# MatrixDriver.net
KiCad netlist of a schematic drawn in Altium Designer
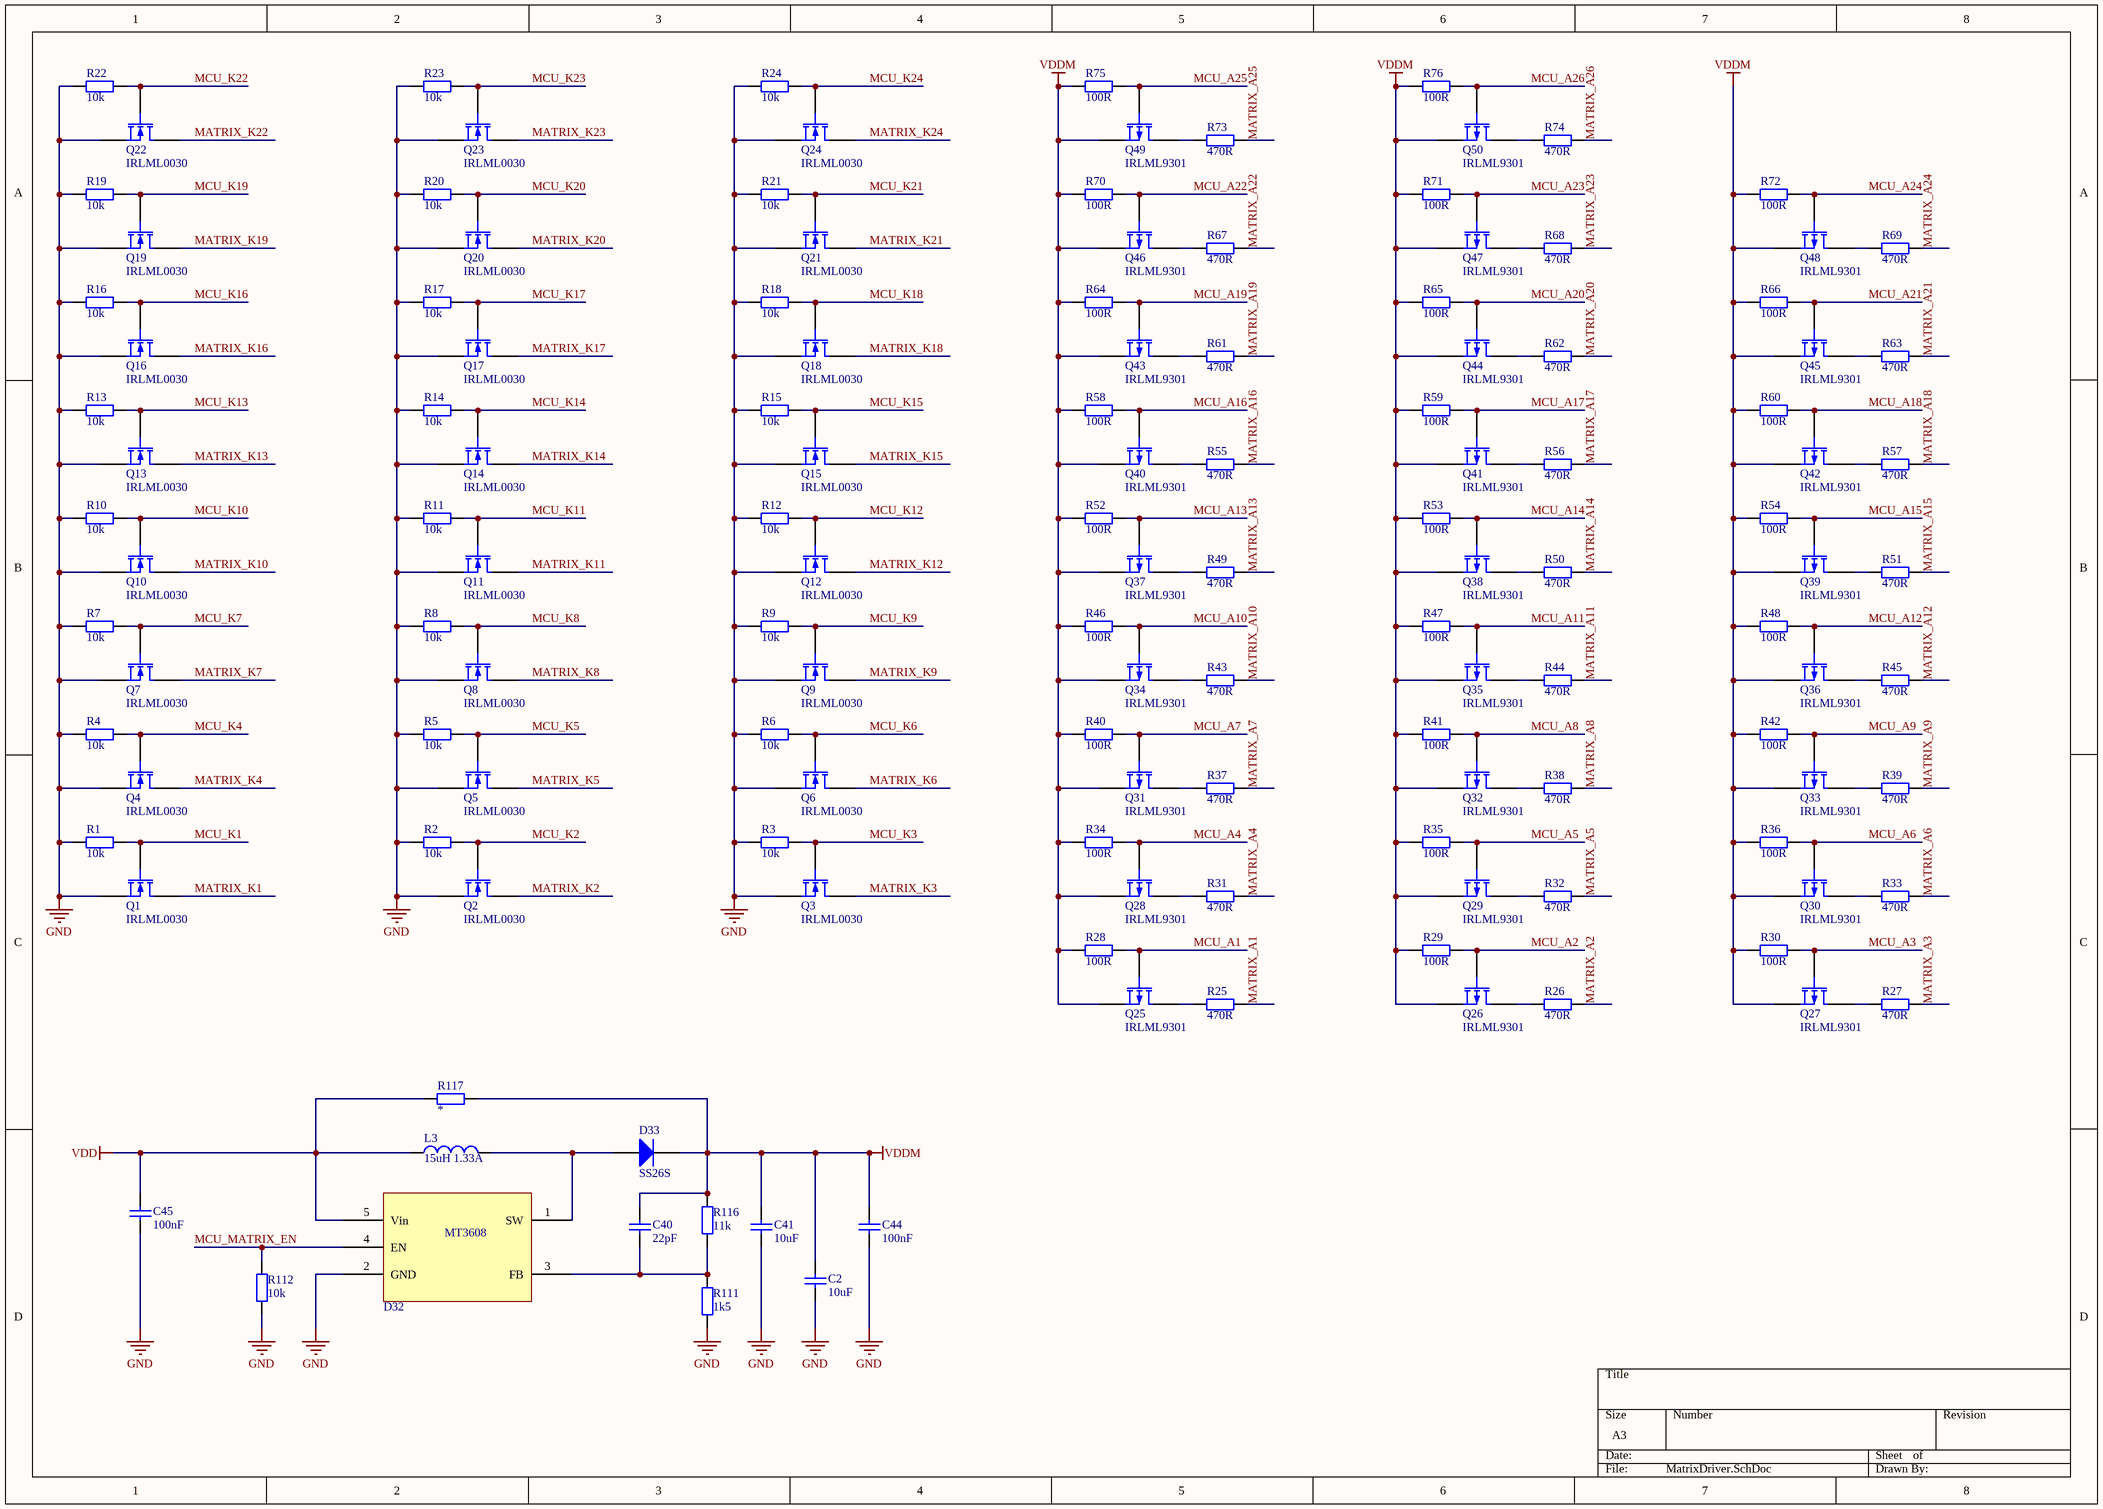
[diagram p0: MatrixDriver.SchDoc]

(export (version "E")
  (design (tool "Eeschema 10.0.6"))
  (components
    (comp (ref "C2")
      (value "10uF")
      (footprint "c1206")
      (description "Capacitor")
      (fields (field (name "Comment") "Cap"))
      (libsource (lib "Lib_Sch") (part "Cap"))
    )
    (comp (ref "C40")
      (value "22pF")
      (footprint "C0603")
      (description "Capacitor")
      (fields (field (name "Comment") "Cap"))
      (libsource (lib "Lib_Sch") (part "Cap"))
    )
    (comp (ref "C41")
      (value "10uF")
      (footprint "c1206")
      (description "Capacitor")
      (fields (field (name "Comment") "Cap"))
      (libsource (lib "Lib_Sch") (part "Cap"))
    )
    (comp (ref "C44")
      (value "100nF")
      (footprint "C0603")
      (description "Capacitor")
      (fields (field (name "Comment") "Cap"))
      (libsource (lib "Lib_Sch") (part "Cap"))
    )
    (comp (ref "C45")
      (value "100nF")
      (footprint "C0603")
      (description "Capacitor")
      (fields (field (name "Comment") "Cap"))
      (libsource (lib "Lib_Sch") (part "Cap"))
    )
    (comp (ref "D32") (value "MT3608") (footprint "SOT23-6_L") (libsource (lib "Lib_Sch") (part "MT3608")))
    (comp (ref "D33")
      (value "SS26S")
      (footprint "DO-214AB")
      (description "Default Diode")
      (libsource (lib "Lib_Sch") (part "Diode"))
    )
    (comp (ref "L3")
      (value "15uH 1.33A")
      (footprint "DE0703")
      (description "DE0703-15")
      (libsource (lib "Lib_Sch") (part "Inductor"))
    )
    (comp (ref "Q1")
      (value "IRLML0030")
      (footprint "sot23")
      (description "N-Channel MOSFET")
      (libsource (lib "Lib_Sch") (part "MOSFET-N"))
    )
    (comp (ref "Q2")
      (value "IRLML0030")
      (footprint "sot23")
      (description "N-Channel MOSFET")
      (libsource (lib "Lib_Sch") (part "MOSFET-N"))
    )
    (comp (ref "Q3")
      (value "IRLML0030")
      (footprint "sot23")
      (description "N-Channel MOSFET")
      (libsource (lib "Lib_Sch") (part "MOSFET-N"))
    )
    (comp (ref "Q4")
      (value "IRLML0030")
      (footprint "sot23")
      (description "N-Channel MOSFET")
      (libsource (lib "Lib_Sch") (part "MOSFET-N"))
    )
    (comp (ref "Q5")
      (value "IRLML0030")
      (footprint "sot23")
      (description "N-Channel MOSFET")
      (libsource (lib "Lib_Sch") (part "MOSFET-N"))
    )
    (comp (ref "Q6")
      (value "IRLML0030")
      (footprint "sot23")
      (description "N-Channel MOSFET")
      (libsource (lib "Lib_Sch") (part "MOSFET-N"))
    )
    (comp (ref "Q7")
      (value "IRLML0030")
      (footprint "sot23")
      (description "N-Channel MOSFET")
      (libsource (lib "Lib_Sch") (part "MOSFET-N"))
    )
    (comp (ref "Q8")
      (value "IRLML0030")
      (footprint "sot23")
      (description "N-Channel MOSFET")
      (libsource (lib "Lib_Sch") (part "MOSFET-N"))
    )
    (comp (ref "Q9")
      (value "IRLML0030")
      (footprint "sot23")
      (description "N-Channel MOSFET")
      (libsource (lib "Lib_Sch") (part "MOSFET-N"))
    )
    (comp (ref "Q10")
      (value "IRLML0030")
      (footprint "sot23")
      (description "N-Channel MOSFET")
      (libsource (lib "Lib_Sch") (part "MOSFET-N"))
    )
    (comp (ref "Q11")
      (value "IRLML0030")
      (footprint "sot23")
      (description "N-Channel MOSFET")
      (libsource (lib "Lib_Sch") (part "MOSFET-N"))
    )
    (comp (ref "Q12")
      (value "IRLML0030")
      (footprint "sot23")
      (description "N-Channel MOSFET")
      (libsource (lib "Lib_Sch") (part "MOSFET-N"))
    )
    (comp (ref "Q13")
      (value "IRLML0030")
      (footprint "sot23")
      (description "N-Channel MOSFET")
      (libsource (lib "Lib_Sch") (part "MOSFET-N"))
    )
    (comp (ref "Q14")
      (value "IRLML0030")
      (footprint "sot23")
      (description "N-Channel MOSFET")
      (libsource (lib "Lib_Sch") (part "MOSFET-N"))
    )
    (comp (ref "Q15")
      (value "IRLML0030")
      (footprint "sot23")
      (description "N-Channel MOSFET")
      (libsource (lib "Lib_Sch") (part "MOSFET-N"))
    )
    (comp (ref "Q16")
      (value "IRLML0030")
      (footprint "sot23")
      (description "N-Channel MOSFET")
      (libsource (lib "Lib_Sch") (part "MOSFET-N"))
    )
    (comp (ref "Q17")
      (value "IRLML0030")
      (footprint "sot23")
      (description "N-Channel MOSFET")
      (libsource (lib "Lib_Sch") (part "MOSFET-N"))
    )
    (comp (ref "Q18")
      (value "IRLML0030")
      (footprint "sot23")
      (description "N-Channel MOSFET")
      (libsource (lib "Lib_Sch") (part "MOSFET-N"))
    )
    (comp (ref "Q19")
      (value "IRLML0030")
      (footprint "sot23")
      (description "N-Channel MOSFET")
      (libsource (lib "Lib_Sch") (part "MOSFET-N"))
    )
    (comp (ref "Q20")
      (value "IRLML0030")
      (footprint "sot23")
      (description "N-Channel MOSFET")
      (libsource (lib "Lib_Sch") (part "MOSFET-N"))
    )
    (comp (ref "Q21")
      (value "IRLML0030")
      (footprint "sot23")
      (description "N-Channel MOSFET")
      (libsource (lib "Lib_Sch") (part "MOSFET-N"))
    )
    (comp (ref "Q22")
      (value "IRLML0030")
      (footprint "sot23")
      (description "N-Channel MOSFET")
      (libsource (lib "Lib_Sch") (part "MOSFET-N"))
    )
    (comp (ref "Q23")
      (value "IRLML0030")
      (footprint "sot23")
      (description "N-Channel MOSFET")
      (libsource (lib "Lib_Sch") (part "MOSFET-N"))
    )
    (comp (ref "Q24")
      (value "IRLML0030")
      (footprint "sot23")
      (description "N-Channel MOSFET")
      (libsource (lib "Lib_Sch") (part "MOSFET-N"))
    )
    (comp (ref "Q25")
      (value "IRLML9301")
      (footprint "sot23")
      (description "P-Channel MOSFET")
      (libsource (lib "Lib_Sch") (part "MOSFET-P"))
    )
    (comp (ref "Q26")
      (value "IRLML9301")
      (footprint "sot23")
      (description "P-Channel MOSFET")
      (libsource (lib "Lib_Sch") (part "MOSFET-P"))
    )
    (comp (ref "Q27")
      (value "IRLML9301")
      (footprint "sot23")
      (description "P-Channel MOSFET")
      (libsource (lib "Lib_Sch") (part "MOSFET-P"))
    )
    (comp (ref "Q28")
      (value "IRLML9301")
      (footprint "sot23")
      (description "P-Channel MOSFET")
      (libsource (lib "Lib_Sch") (part "MOSFET-P"))
    )
    (comp (ref "Q29")
      (value "IRLML9301")
      (footprint "sot23")
      (description "P-Channel MOSFET")
      (libsource (lib "Lib_Sch") (part "MOSFET-P"))
    )
    (comp (ref "Q30")
      (value "IRLML9301")
      (footprint "sot23")
      (description "P-Channel MOSFET")
      (libsource (lib "Lib_Sch") (part "MOSFET-P"))
    )
    (comp (ref "Q31")
      (value "IRLML9301")
      (footprint "sot23")
      (description "P-Channel MOSFET")
      (libsource (lib "Lib_Sch") (part "MOSFET-P"))
    )
    (comp (ref "Q32")
      (value "IRLML9301")
      (footprint "sot23")
      (description "P-Channel MOSFET")
      (libsource (lib "Lib_Sch") (part "MOSFET-P"))
    )
    (comp (ref "Q33")
      (value "IRLML9301")
      (footprint "sot23")
      (description "P-Channel MOSFET")
      (libsource (lib "Lib_Sch") (part "MOSFET-P"))
    )
    (comp (ref "Q34")
      (value "IRLML9301")
      (footprint "sot23")
      (description "P-Channel MOSFET")
      (libsource (lib "Lib_Sch") (part "MOSFET-P"))
    )
    (comp (ref "Q35")
      (value "IRLML9301")
      (footprint "sot23")
      (description "P-Channel MOSFET")
      (libsource (lib "Lib_Sch") (part "MOSFET-P"))
    )
    (comp (ref "Q36")
      (value "IRLML9301")
      (footprint "sot23")
      (description "P-Channel MOSFET")
      (libsource (lib "Lib_Sch") (part "MOSFET-P"))
    )
    (comp (ref "Q37")
      (value "IRLML9301")
      (footprint "sot23")
      (description "P-Channel MOSFET")
      (libsource (lib "Lib_Sch") (part "MOSFET-P"))
    )
    (comp (ref "Q38")
      (value "IRLML9301")
      (footprint "sot23")
      (description "P-Channel MOSFET")
      (libsource (lib "Lib_Sch") (part "MOSFET-P"))
    )
    (comp (ref "Q39")
      (value "IRLML9301")
      (footprint "sot23")
      (description "P-Channel MOSFET")
      (libsource (lib "Lib_Sch") (part "MOSFET-P"))
    )
    (comp (ref "Q40")
      (value "IRLML9301")
      (footprint "sot23")
      (description "P-Channel MOSFET")
      (libsource (lib "Lib_Sch") (part "MOSFET-P"))
    )
    (comp (ref "Q41")
      (value "IRLML9301")
      (footprint "sot23")
      (description "P-Channel MOSFET")
      (libsource (lib "Lib_Sch") (part "MOSFET-P"))
    )
    (comp (ref "Q42")
      (value "IRLML9301")
      (footprint "sot23")
      (description "P-Channel MOSFET")
      (libsource (lib "Lib_Sch") (part "MOSFET-P"))
    )
    (comp (ref "Q43")
      (value "IRLML9301")
      (footprint "sot23")
      (description "P-Channel MOSFET")
      (libsource (lib "Lib_Sch") (part "MOSFET-P"))
    )
    (comp (ref "Q44")
      (value "IRLML9301")
      (footprint "sot23")
      (description "P-Channel MOSFET")
      (libsource (lib "Lib_Sch") (part "MOSFET-P"))
    )
    (comp (ref "Q45")
      (value "IRLML9301")
      (footprint "sot23")
      (description "P-Channel MOSFET")
      (libsource (lib "Lib_Sch") (part "MOSFET-P"))
    )
    (comp (ref "Q46")
      (value "IRLML9301")
      (footprint "sot23")
      (description "P-Channel MOSFET")
      (libsource (lib "Lib_Sch") (part "MOSFET-P"))
    )
    (comp (ref "Q47")
      (value "IRLML9301")
      (footprint "sot23")
      (description "P-Channel MOSFET")
      (libsource (lib "Lib_Sch") (part "MOSFET-P"))
    )
    (comp (ref "Q48")
      (value "IRLML9301")
      (footprint "sot23")
      (description "P-Channel MOSFET")
      (libsource (lib "Lib_Sch") (part "MOSFET-P"))
    )
    (comp (ref "Q49")
      (value "IRLML9301")
      (footprint "sot23")
      (description "P-Channel MOSFET")
      (libsource (lib "Lib_Sch") (part "MOSFET-P"))
    )
    (comp (ref "Q50")
      (value "IRLML9301")
      (footprint "sot23")
      (description "P-Channel MOSFET")
      (libsource (lib "Lib_Sch") (part "MOSFET-P"))
    )
    (comp (ref "R1")
      (value "10k")
      (footprint "r0603")
      (description "Resistor")
      (libsource (lib "Lib_Sch") (part "Resistor"))
    )
    (comp (ref "R2")
      (value "10k")
      (footprint "r0603")
      (description "Resistor")
      (libsource (lib "Lib_Sch") (part "Resistor"))
    )
    (comp (ref "R3")
      (value "10k")
      (footprint "r0603")
      (description "Resistor")
      (libsource (lib "Lib_Sch") (part "Resistor"))
    )
    (comp (ref "R4")
      (value "10k")
      (footprint "r0603")
      (description "Resistor")
      (libsource (lib "Lib_Sch") (part "Resistor"))
    )
    (comp (ref "R5")
      (value "10k")
      (footprint "r0603")
      (description "Resistor")
      (libsource (lib "Lib_Sch") (part "Resistor"))
    )
    (comp (ref "R6")
      (value "10k")
      (footprint "r0603")
      (description "Resistor")
      (libsource (lib "Lib_Sch") (part "Resistor"))
    )
    (comp (ref "R7")
      (value "10k")
      (footprint "r0603")
      (description "Resistor")
      (libsource (lib "Lib_Sch") (part "Resistor"))
    )
    (comp (ref "R8")
      (value "10k")
      (footprint "r0603")
      (description "Resistor")
      (libsource (lib "Lib_Sch") (part "Resistor"))
    )
    (comp (ref "R9")
      (value "10k")
      (footprint "r0603")
      (description "Resistor")
      (libsource (lib "Lib_Sch") (part "Resistor"))
    )
    (comp (ref "R10")
      (value "10k")
      (footprint "r0603")
      (description "Resistor")
      (libsource (lib "Lib_Sch") (part "Resistor"))
    )
    (comp (ref "R11")
      (value "10k")
      (footprint "r0603")
      (description "Resistor")
      (libsource (lib "Lib_Sch") (part "Resistor"))
    )
    (comp (ref "R12")
      (value "10k")
      (footprint "r0603")
      (description "Resistor")
      (libsource (lib "Lib_Sch") (part "Resistor"))
    )
    (comp (ref "R13")
      (value "10k")
      (footprint "r0603")
      (description "Resistor")
      (libsource (lib "Lib_Sch") (part "Resistor"))
    )
    (comp (ref "R14")
      (value "10k")
      (footprint "r0603")
      (description "Resistor")
      (libsource (lib "Lib_Sch") (part "Resistor"))
    )
    (comp (ref "R15")
      (value "10k")
      (footprint "r0603")
      (description "Resistor")
      (libsource (lib "Lib_Sch") (part "Resistor"))
    )
    (comp (ref "R16")
      (value "10k")
      (footprint "r0603")
      (description "Resistor")
      (libsource (lib "Lib_Sch") (part "Resistor"))
    )
    (comp (ref "R17")
      (value "10k")
      (footprint "r0603")
      (description "Resistor")
      (libsource (lib "Lib_Sch") (part "Resistor"))
    )
    (comp (ref "R18")
      (value "10k")
      (footprint "r0603")
      (description "Resistor")
      (libsource (lib "Lib_Sch") (part "Resistor"))
    )
    (comp (ref "R19")
      (value "10k")
      (footprint "r0603")
      (description "Resistor")
      (libsource (lib "Lib_Sch") (part "Resistor"))
    )
    (comp (ref "R20")
      (value "10k")
      (footprint "r0603")
      (description "Resistor")
      (libsource (lib "Lib_Sch") (part "Resistor"))
    )
    (comp (ref "R21")
      (value "10k")
      (footprint "r0603")
      (description "Resistor")
      (libsource (lib "Lib_Sch") (part "Resistor"))
    )
    (comp (ref "R22")
      (value "10k")
      (footprint "r0603")
      (description "Resistor")
      (libsource (lib "Lib_Sch") (part "Resistor"))
    )
    (comp (ref "R23")
      (value "10k")
      (footprint "r0603")
      (description "Resistor")
      (libsource (lib "Lib_Sch") (part "Resistor"))
    )
    (comp (ref "R24")
      (value "10k")
      (footprint "r0603")
      (description "Resistor")
      (libsource (lib "Lib_Sch") (part "Resistor"))
    )
    (comp (ref "R25")
      (value "470R")
      (footprint "r0603")
      (description "Resistor")
      (libsource (lib "Lib_Sch") (part "Resistor"))
    )
    (comp (ref "R26")
      (value "470R")
      (footprint "r0603")
      (description "Resistor")
      (libsource (lib "Lib_Sch") (part "Resistor"))
    )
    (comp (ref "R27")
      (value "470R")
      (footprint "r0603")
      (description "Resistor")
      (libsource (lib "Lib_Sch") (part "Resistor"))
    )
    (comp (ref "R28")
      (value "100R")
      (footprint "r0603")
      (description "Resistor")
      (libsource (lib "Lib_Sch") (part "Resistor"))
    )
    (comp (ref "R29")
      (value "100R")
      (footprint "r0603")
      (description "Resistor")
      (libsource (lib "Lib_Sch") (part "Resistor"))
    )
    (comp (ref "R30")
      (value "100R")
      (footprint "r0603")
      (description "Resistor")
      (libsource (lib "Lib_Sch") (part "Resistor"))
    )
    (comp (ref "R31")
      (value "470R")
      (footprint "r0603")
      (description "Resistor")
      (libsource (lib "Lib_Sch") (part "Resistor"))
    )
    (comp (ref "R32")
      (value "470R")
      (footprint "r0603")
      (description "Resistor")
      (libsource (lib "Lib_Sch") (part "Resistor"))
    )
    (comp (ref "R33")
      (value "470R")
      (footprint "r0603")
      (description "Resistor")
      (libsource (lib "Lib_Sch") (part "Resistor"))
    )
    (comp (ref "R34")
      (value "100R")
      (footprint "r0603")
      (description "Resistor")
      (libsource (lib "Lib_Sch") (part "Resistor"))
    )
    (comp (ref "R35")
      (value "100R")
      (footprint "r0603")
      (description "Resistor")
      (libsource (lib "Lib_Sch") (part "Resistor"))
    )
    (comp (ref "R36")
      (value "100R")
      (footprint "r0603")
      (description "Resistor")
      (libsource (lib "Lib_Sch") (part "Resistor"))
    )
    (comp (ref "R37")
      (value "470R")
      (footprint "r0603")
      (description "Resistor")
      (libsource (lib "Lib_Sch") (part "Resistor"))
    )
    (comp (ref "R38")
      (value "470R")
      (footprint "r0603")
      (description "Resistor")
      (libsource (lib "Lib_Sch") (part "Resistor"))
    )
    (comp (ref "R39")
      (value "470R")
      (footprint "r0603")
      (description "Resistor")
      (libsource (lib "Lib_Sch") (part "Resistor"))
    )
    (comp (ref "R40")
      (value "100R")
      (footprint "r0603")
      (description "Resistor")
      (libsource (lib "Lib_Sch") (part "Resistor"))
    )
    (comp (ref "R41")
      (value "100R")
      (footprint "r0603")
      (description "Resistor")
      (libsource (lib "Lib_Sch") (part "Resistor"))
    )
    (comp (ref "R42")
      (value "100R")
      (footprint "r0603")
      (description "Resistor")
      (libsource (lib "Lib_Sch") (part "Resistor"))
    )
    (comp (ref "R43")
      (value "470R")
      (footprint "r0603")
      (description "Resistor")
      (libsource (lib "Lib_Sch") (part "Resistor"))
    )
    (comp (ref "R44")
      (value "470R")
      (footprint "r0603")
      (description "Resistor")
      (libsource (lib "Lib_Sch") (part "Resistor"))
    )
    (comp (ref "R45")
      (value "470R")
      (footprint "r0603")
      (description "Resistor")
      (libsource (lib "Lib_Sch") (part "Resistor"))
    )
    (comp (ref "R46")
      (value "100R")
      (footprint "r0603")
      (description "Resistor")
      (libsource (lib "Lib_Sch") (part "Resistor"))
    )
    (comp (ref "R47")
      (value "100R")
      (footprint "r0603")
      (description "Resistor")
      (libsource (lib "Lib_Sch") (part "Resistor"))
    )
    (comp (ref "R48")
      (value "100R")
      (footprint "r0603")
      (description "Resistor")
      (libsource (lib "Lib_Sch") (part "Resistor"))
    )
    (comp (ref "R49")
      (value "470R")
      (footprint "r0603")
      (description "Resistor")
      (libsource (lib "Lib_Sch") (part "Resistor"))
    )
    (comp (ref "R50")
      (value "470R")
      (footprint "r0603")
      (description "Resistor")
      (libsource (lib "Lib_Sch") (part "Resistor"))
    )
    (comp (ref "R51")
      (value "470R")
      (footprint "r0603")
      (description "Resistor")
      (libsource (lib "Lib_Sch") (part "Resistor"))
    )
    (comp (ref "R52")
      (value "100R")
      (footprint "r0603")
      (description "Resistor")
      (libsource (lib "Lib_Sch") (part "Resistor"))
    )
    (comp (ref "R53")
      (value "100R")
      (footprint "r0603")
      (description "Resistor")
      (libsource (lib "Lib_Sch") (part "Resistor"))
    )
    (comp (ref "R54")
      (value "100R")
      (footprint "r0603")
      (description "Resistor")
      (libsource (lib "Lib_Sch") (part "Resistor"))
    )
    (comp (ref "R55")
      (value "470R")
      (footprint "r0603")
      (description "Resistor")
      (libsource (lib "Lib_Sch") (part "Resistor"))
    )
    (comp (ref "R56")
      (value "470R")
      (footprint "r0603")
      (description "Resistor")
      (libsource (lib "Lib_Sch") (part "Resistor"))
    )
    (comp (ref "R57")
      (value "470R")
      (footprint "r0603")
      (description "Resistor")
      (libsource (lib "Lib_Sch") (part "Resistor"))
    )
    (comp (ref "R58")
      (value "100R")
      (footprint "r0603")
      (description "Resistor")
      (libsource (lib "Lib_Sch") (part "Resistor"))
    )
    (comp (ref "R59")
      (value "100R")
      (footprint "r0603")
      (description "Resistor")
      (libsource (lib "Lib_Sch") (part "Resistor"))
    )
    (comp (ref "R60")
      (value "100R")
      (footprint "r0603")
      (description "Resistor")
      (libsource (lib "Lib_Sch") (part "Resistor"))
    )
    (comp (ref "R61")
      (value "470R")
      (footprint "r0603")
      (description "Resistor")
      (libsource (lib "Lib_Sch") (part "Resistor"))
    )
    (comp (ref "R62")
      (value "470R")
      (footprint "r0603")
      (description "Resistor")
      (libsource (lib "Lib_Sch") (part "Resistor"))
    )
    (comp (ref "R63")
      (value "470R")
      (footprint "r0603")
      (description "Resistor")
      (libsource (lib "Lib_Sch") (part "Resistor"))
    )
    (comp (ref "R64")
      (value "100R")
      (footprint "r0603")
      (description "Resistor")
      (libsource (lib "Lib_Sch") (part "Resistor"))
    )
    (comp (ref "R65")
      (value "100R")
      (footprint "r0603")
      (description "Resistor")
      (libsource (lib "Lib_Sch") (part "Resistor"))
    )
    (comp (ref "R66")
      (value "100R")
      (footprint "r0603")
      (description "Resistor")
      (libsource (lib "Lib_Sch") (part "Resistor"))
    )
    (comp (ref "R67")
      (value "470R")
      (footprint "r0603")
      (description "Resistor")
      (libsource (lib "Lib_Sch") (part "Resistor"))
    )
    (comp (ref "R68")
      (value "470R")
      (footprint "r0603")
      (description "Resistor")
      (libsource (lib "Lib_Sch") (part "Resistor"))
    )
    (comp (ref "R69")
      (value "470R")
      (footprint "r0603")
      (description "Resistor")
      (libsource (lib "Lib_Sch") (part "Resistor"))
    )
    (comp (ref "R70")
      (value "100R")
      (footprint "r0603")
      (description "Resistor")
      (libsource (lib "Lib_Sch") (part "Resistor"))
    )
    (comp (ref "R71")
      (value "100R")
      (footprint "r0603")
      (description "Resistor")
      (libsource (lib "Lib_Sch") (part "Resistor"))
    )
    (comp (ref "R72")
      (value "100R")
      (footprint "r0603")
      (description "Resistor")
      (libsource (lib "Lib_Sch") (part "Resistor"))
    )
    (comp (ref "R73")
      (value "470R")
      (footprint "r0603")
      (description "Resistor")
      (libsource (lib "Lib_Sch") (part "Resistor"))
    )
    (comp (ref "R74")
      (value "470R")
      (footprint "r0603")
      (description "Resistor")
      (libsource (lib "Lib_Sch") (part "Resistor"))
    )
    (comp (ref "R75")
      (value "100R")
      (footprint "r0603")
      (description "Resistor")
      (libsource (lib "Lib_Sch") (part "Resistor"))
    )
    (comp (ref "R76")
      (value "100R")
      (footprint "r0603")
      (description "Resistor")
      (libsource (lib "Lib_Sch") (part "Resistor"))
    )
    (comp (ref "R111")
      (value "1k5")
      (footprint "r0603")
      (description "Resistor")
      (libsource (lib "") (part "Resistor_1"))
    )
    (comp (ref "R112")
      (value "10k")
      (footprint "r0603")
      (description "Resistor")
      (libsource (lib "") (part "Resistor_1"))
    )
    (comp (ref "R116")
      (value "11k")
      (footprint "r0603")
      (description "Resistor")
      (libsource (lib "") (part "Resistor_1"))
    )
    (comp (ref "R117")
      (value "Resistor")
      (footprint "n0603")
      (fields (field (name "ALTIUM_VALUE") "*"))
      (libsource (lib "") (part "Resistor_2"))
    )
  )
  (nets
    (net (code "1") (name "/MATRIX_A1") (class "Default")
      (node (ref "R25") (pin "2") (pinfunction "2_2") (pintype "passive"))
    )
    (net (code "2") (name "/MATRIX_A2") (class "Default")
      (node (ref "R26") (pin "2") (pinfunction "2_2") (pintype "passive"))
    )
    (net (code "3") (name "/MATRIX_A3") (class "Default")
      (node (ref "R27") (pin "2") (pinfunction "2_2") (pintype "passive"))
    )
    (net (code "4") (name "/MATRIX_A4") (class "Default")
      (node (ref "R31") (pin "2") (pinfunction "2_2") (pintype "passive"))
    )
    (net (code "5") (name "/MATRIX_A5") (class "Default")
      (node (ref "R32") (pin "2") (pinfunction "2_2") (pintype "passive"))
    )
    (net (code "6") (name "/MATRIX_A6") (class "Default")
      (node (ref "R33") (pin "2") (pinfunction "2_2") (pintype "passive"))
    )
    (net (code "7") (name "/MATRIX_A7") (class "Default")
      (node (ref "R37") (pin "2") (pinfunction "2_2") (pintype "passive"))
    )
    (net (code "8") (name "/MATRIX_A8") (class "Default")
      (node (ref "R38") (pin "2") (pinfunction "2_2") (pintype "passive"))
    )
    (net (code "9") (name "/MATRIX_A9") (class "Default")
      (node (ref "R39") (pin "2") (pinfunction "2_2") (pintype "passive"))
    )
    (net (code "10") (name "/MATRIX_A10") (class "Default")
      (node (ref "R43") (pin "2") (pinfunction "2_2") (pintype "passive"))
    )
    (net (code "11") (name "/MATRIX_A11") (class "Default")
      (node (ref "R44") (pin "2") (pinfunction "2_2") (pintype "passive"))
    )
    (net (code "12") (name "/MATRIX_A12") (class "Default")
      (node (ref "R45") (pin "2") (pinfunction "2_2") (pintype "passive"))
    )
    (net (code "13") (name "/MATRIX_A13") (class "Default")
      (node (ref "R49") (pin "2") (pinfunction "2_2") (pintype "passive"))
    )
    (net (code "14") (name "/MATRIX_A14") (class "Default")
      (node (ref "R50") (pin "2") (pinfunction "2_2") (pintype "passive"))
    )
    (net (code "15") (name "/MATRIX_A15") (class "Default")
      (node (ref "R51") (pin "2") (pinfunction "2_2") (pintype "passive"))
    )
    (net (code "16") (name "/MATRIX_A16") (class "Default")
      (node (ref "R55") (pin "2") (pinfunction "2_2") (pintype "passive"))
    )
    (net (code "17") (name "/MATRIX_A17") (class "Default")
      (node (ref "R56") (pin "2") (pinfunction "2_2") (pintype "passive"))
    )
    (net (code "18") (name "/MATRIX_A18") (class "Default")
      (node (ref "R57") (pin "2") (pinfunction "2_2") (pintype "passive"))
    )
    (net (code "19") (name "/MATRIX_A19") (class "Default")
      (node (ref "R61") (pin "2") (pinfunction "2_2") (pintype "passive"))
    )
    (net (code "20") (name "/MATRIX_A20") (class "Default")
      (node (ref "R62") (pin "2") (pinfunction "2_2") (pintype "passive"))
    )
    (net (code "21") (name "/MATRIX_A21") (class "Default")
      (node (ref "R63") (pin "2") (pinfunction "2_2") (pintype "passive"))
    )
    (net (code "22") (name "/MATRIX_A22") (class "Default")
      (node (ref "R67") (pin "2") (pinfunction "2_2") (pintype "passive"))
    )
    (net (code "23") (name "/MATRIX_A23") (class "Default")
      (node (ref "R68") (pin "2") (pinfunction "2_2") (pintype "passive"))
    )
    (net (code "24") (name "/MATRIX_A24") (class "Default")
      (node (ref "R69") (pin "2") (pinfunction "2_2") (pintype "passive"))
    )
    (net (code "25") (name "/MATRIX_A25") (class "Default")
      (node (ref "R73") (pin "2") (pinfunction "2_2") (pintype "passive"))
    )
    (net (code "26") (name "/MATRIX_A26") (class "Default")
      (node (ref "R74") (pin "2") (pinfunction "2_2") (pintype "passive"))
    )
    (net (code "27") (name "/MATRIX_K1") (class "Default")
      (node (ref "Q1") (pin "3") (pinfunction "D_3") (pintype "passive"))
    )
    (net (code "28") (name "/MATRIX_K2") (class "Default")
      (node (ref "Q2") (pin "3") (pinfunction "D_3") (pintype "passive"))
    )
    (net (code "29") (name "/MATRIX_K3") (class "Default")
      (node (ref "Q3") (pin "3") (pinfunction "D_3") (pintype "passive"))
    )
    (net (code "30") (name "/MATRIX_K4") (class "Default")
      (node (ref "Q4") (pin "3") (pinfunction "D_3") (pintype "passive"))
    )
    (net (code "31") (name "/MATRIX_K5") (class "Default")
      (node (ref "Q5") (pin "3") (pinfunction "D_3") (pintype "passive"))
    )
    (net (code "32") (name "/MATRIX_K6") (class "Default")
      (node (ref "Q6") (pin "3") (pinfunction "D_3") (pintype "passive"))
    )
    (net (code "33") (name "/MATRIX_K7") (class "Default")
      (node (ref "Q7") (pin "3") (pinfunction "D_3") (pintype "passive"))
    )
    (net (code "34") (name "/MATRIX_K8") (class "Default")
      (node (ref "Q8") (pin "3") (pinfunction "D_3") (pintype "passive"))
    )
    (net (code "35") (name "/MATRIX_K9") (class "Default")
      (node (ref "Q9") (pin "3") (pinfunction "D_3") (pintype "passive"))
    )
    (net (code "36") (name "/MATRIX_K10") (class "Default")
      (node (ref "Q10") (pin "3") (pinfunction "D_3") (pintype "passive"))
    )
    (net (code "37") (name "/MATRIX_K11") (class "Default")
      (node (ref "Q11") (pin "3") (pinfunction "D_3") (pintype "passive"))
    )
    (net (code "38") (name "/MATRIX_K12") (class "Default")
      (node (ref "Q12") (pin "3") (pinfunction "D_3") (pintype "passive"))
    )
    (net (code "39") (name "/MATRIX_K13") (class "Default")
      (node (ref "Q13") (pin "3") (pinfunction "D_3") (pintype "passive"))
    )
    (net (code "40") (name "/MATRIX_K14") (class "Default")
      (node (ref "Q14") (pin "3") (pinfunction "D_3") (pintype "passive"))
    )
    (net (code "41") (name "/MATRIX_K15") (class "Default")
      (node (ref "Q15") (pin "3") (pinfunction "D_3") (pintype "passive"))
    )
    (net (code "42") (name "/MATRIX_K16") (class "Default")
      (node (ref "Q16") (pin "3") (pinfunction "D_3") (pintype "passive"))
    )
    (net (code "43") (name "/MATRIX_K17") (class "Default")
      (node (ref "Q17") (pin "3") (pinfunction "D_3") (pintype "passive"))
    )
    (net (code "44") (name "/MATRIX_K18") (class "Default")
      (node (ref "Q18") (pin "3") (pinfunction "D_3") (pintype "passive"))
    )
    (net (code "45") (name "/MATRIX_K19") (class "Default")
      (node (ref "Q19") (pin "3") (pinfunction "D_3") (pintype "passive"))
    )
    (net (code "46") (name "/MATRIX_K20") (class "Default")
      (node (ref "Q20") (pin "3") (pinfunction "D_3") (pintype "passive"))
    )
    (net (code "47") (name "/MATRIX_K21") (class "Default")
      (node (ref "Q21") (pin "3") (pinfunction "D_3") (pintype "passive"))
    )
    (net (code "48") (name "/MATRIX_K22") (class "Default")
      (node (ref "Q22") (pin "3") (pinfunction "D_3") (pintype "passive"))
    )
    (net (code "49") (name "/MATRIX_K23") (class "Default")
      (node (ref "Q23") (pin "3") (pinfunction "D_3") (pintype "passive"))
    )
    (net (code "50") (name "/MATRIX_K24") (class "Default")
      (node (ref "Q24") (pin "3") (pinfunction "D_3") (pintype "passive"))
    )
    (net (code "51") (name "/MCU_A1") (class "Default")
      (node (ref "Q25") (pin "1") (pinfunction "G_1") (pintype "passive"))
      (node (ref "R28") (pin "2") (pinfunction "2_2") (pintype "passive"))
    )
    (net (code "52") (name "/MCU_A2") (class "Default")
      (node (ref "Q26") (pin "1") (pinfunction "G_1") (pintype "passive"))
      (node (ref "R29") (pin "2") (pinfunction "2_2") (pintype "passive"))
    )
    (net (code "53") (name "/MCU_A3") (class "Default")
      (node (ref "Q27") (pin "1") (pinfunction "G_1") (pintype "passive"))
      (node (ref "R30") (pin "2") (pinfunction "2_2") (pintype "passive"))
    )
    (net (code "54") (name "/MCU_A4") (class "Default")
      (node (ref "Q28") (pin "1") (pinfunction "G_1") (pintype "passive"))
      (node (ref "R34") (pin "2") (pinfunction "2_2") (pintype "passive"))
    )
    (net (code "55") (name "/MCU_A5") (class "Default")
      (node (ref "Q29") (pin "1") (pinfunction "G_1") (pintype "passive"))
      (node (ref "R35") (pin "2") (pinfunction "2_2") (pintype "passive"))
    )
    (net (code "56") (name "/MCU_A6") (class "Default")
      (node (ref "Q30") (pin "1") (pinfunction "G_1") (pintype "passive"))
      (node (ref "R36") (pin "2") (pinfunction "2_2") (pintype "passive"))
    )
    (net (code "57") (name "/MCU_A7") (class "Default")
      (node (ref "Q31") (pin "1") (pinfunction "G_1") (pintype "passive"))
      (node (ref "R40") (pin "2") (pinfunction "2_2") (pintype "passive"))
    )
    (net (code "58") (name "/MCU_A8") (class "Default")
      (node (ref "Q32") (pin "1") (pinfunction "G_1") (pintype "passive"))
      (node (ref "R41") (pin "2") (pinfunction "2_2") (pintype "passive"))
    )
    (net (code "59") (name "/MCU_A9") (class "Default")
      (node (ref "Q33") (pin "1") (pinfunction "G_1") (pintype "passive"))
      (node (ref "R42") (pin "2") (pinfunction "2_2") (pintype "passive"))
    )
    (net (code "60") (name "/MCU_A10") (class "Default")
      (node (ref "Q34") (pin "1") (pinfunction "G_1") (pintype "passive"))
      (node (ref "R46") (pin "2") (pinfunction "2_2") (pintype "passive"))
    )
    (net (code "61") (name "/MCU_A11") (class "Default")
      (node (ref "Q35") (pin "1") (pinfunction "G_1") (pintype "passive"))
      (node (ref "R47") (pin "2") (pinfunction "2_2") (pintype "passive"))
    )
    (net (code "62") (name "/MCU_A12") (class "Default")
      (node (ref "Q36") (pin "1") (pinfunction "G_1") (pintype "passive"))
      (node (ref "R48") (pin "2") (pinfunction "2_2") (pintype "passive"))
    )
    (net (code "63") (name "/MCU_A13") (class "Default")
      (node (ref "Q37") (pin "1") (pinfunction "G_1") (pintype "passive"))
      (node (ref "R52") (pin "2") (pinfunction "2_2") (pintype "passive"))
    )
    (net (code "64") (name "/MCU_A14") (class "Default")
      (node (ref "Q38") (pin "1") (pinfunction "G_1") (pintype "passive"))
      (node (ref "R53") (pin "2") (pinfunction "2_2") (pintype "passive"))
    )
    (net (code "65") (name "/MCU_A15") (class "Default")
      (node (ref "Q39") (pin "1") (pinfunction "G_1") (pintype "passive"))
      (node (ref "R54") (pin "2") (pinfunction "2_2") (pintype "passive"))
    )
    (net (code "66") (name "/MCU_A16") (class "Default")
      (node (ref "Q40") (pin "1") (pinfunction "G_1") (pintype "passive"))
      (node (ref "R58") (pin "2") (pinfunction "2_2") (pintype "passive"))
    )
    (net (code "67") (name "/MCU_A17") (class "Default")
      (node (ref "Q41") (pin "1") (pinfunction "G_1") (pintype "passive"))
      (node (ref "R59") (pin "2") (pinfunction "2_2") (pintype "passive"))
    )
    (net (code "68") (name "/MCU_A18") (class "Default")
      (node (ref "Q42") (pin "1") (pinfunction "G_1") (pintype "passive"))
      (node (ref "R60") (pin "2") (pinfunction "2_2") (pintype "passive"))
    )
    (net (code "69") (name "/MCU_A19") (class "Default")
      (node (ref "Q43") (pin "1") (pinfunction "G_1") (pintype "passive"))
      (node (ref "R64") (pin "2") (pinfunction "2_2") (pintype "passive"))
    )
    (net (code "70") (name "/MCU_A20") (class "Default")
      (node (ref "Q44") (pin "1") (pinfunction "G_1") (pintype "passive"))
      (node (ref "R65") (pin "2") (pinfunction "2_2") (pintype "passive"))
    )
    (net (code "71") (name "/MCU_A21") (class "Default")
      (node (ref "Q45") (pin "1") (pinfunction "G_1") (pintype "passive"))
      (node (ref "R66") (pin "2") (pinfunction "2_2") (pintype "passive"))
    )
    (net (code "72") (name "/MCU_A22") (class "Default")
      (node (ref "Q46") (pin "1") (pinfunction "G_1") (pintype "passive"))
      (node (ref "R70") (pin "2") (pinfunction "2_2") (pintype "passive"))
    )
    (net (code "73") (name "/MCU_A23") (class "Default")
      (node (ref "Q47") (pin "1") (pinfunction "G_1") (pintype "passive"))
      (node (ref "R71") (pin "2") (pinfunction "2_2") (pintype "passive"))
    )
    (net (code "74") (name "/MCU_A24") (class "Default")
      (node (ref "Q48") (pin "1") (pinfunction "G_1") (pintype "passive"))
      (node (ref "R72") (pin "2") (pinfunction "2_2") (pintype "passive"))
    )
    (net (code "75") (name "/MCU_A25") (class "Default")
      (node (ref "Q49") (pin "1") (pinfunction "G_1") (pintype "passive"))
      (node (ref "R75") (pin "2") (pinfunction "2_2") (pintype "passive"))
    )
    (net (code "76") (name "/MCU_A26") (class "Default")
      (node (ref "Q50") (pin "1") (pinfunction "G_1") (pintype "passive"))
      (node (ref "R76") (pin "2") (pinfunction "2_2") (pintype "passive"))
    )
    (net (code "77") (name "/MCU_K1") (class "Default")
      (node (ref "Q1") (pin "1") (pinfunction "G_1") (pintype "passive"))
      (node (ref "R1") (pin "2") (pinfunction "2_2") (pintype "passive"))
    )
    (net (code "78") (name "/MCU_K2") (class "Default")
      (node (ref "Q2") (pin "1") (pinfunction "G_1") (pintype "passive"))
      (node (ref "R2") (pin "2") (pinfunction "2_2") (pintype "passive"))
    )
    (net (code "79") (name "/MCU_K3") (class "Default")
      (node (ref "Q3") (pin "1") (pinfunction "G_1") (pintype "passive"))
      (node (ref "R3") (pin "2") (pinfunction "2_2") (pintype "passive"))
    )
    (net (code "80") (name "/MCU_K4") (class "Default")
      (node (ref "Q4") (pin "1") (pinfunction "G_1") (pintype "passive"))
      (node (ref "R4") (pin "2") (pinfunction "2_2") (pintype "passive"))
    )
    (net (code "81") (name "/MCU_K5") (class "Default")
      (node (ref "Q5") (pin "1") (pinfunction "G_1") (pintype "passive"))
      (node (ref "R5") (pin "2") (pinfunction "2_2") (pintype "passive"))
    )
    (net (code "82") (name "/MCU_K6") (class "Default")
      (node (ref "Q6") (pin "1") (pinfunction "G_1") (pintype "passive"))
      (node (ref "R6") (pin "2") (pinfunction "2_2") (pintype "passive"))
    )
    (net (code "83") (name "/MCU_K7") (class "Default")
      (node (ref "Q7") (pin "1") (pinfunction "G_1") (pintype "passive"))
      (node (ref "R7") (pin "2") (pinfunction "2_2") (pintype "passive"))
    )
    (net (code "84") (name "/MCU_K8") (class "Default")
      (node (ref "Q8") (pin "1") (pinfunction "G_1") (pintype "passive"))
      (node (ref "R8") (pin "2") (pinfunction "2_2") (pintype "passive"))
    )
    (net (code "85") (name "/MCU_K9") (class "Default")
      (node (ref "Q9") (pin "1") (pinfunction "G_1") (pintype "passive"))
      (node (ref "R9") (pin "2") (pinfunction "2_2") (pintype "passive"))
    )
    (net (code "86") (name "/MCU_K10") (class "Default")
      (node (ref "Q10") (pin "1") (pinfunction "G_1") (pintype "passive"))
      (node (ref "R10") (pin "2") (pinfunction "2_2") (pintype "passive"))
    )
    (net (code "87") (name "/MCU_K11") (class "Default")
      (node (ref "Q11") (pin "1") (pinfunction "G_1") (pintype "passive"))
      (node (ref "R11") (pin "2") (pinfunction "2_2") (pintype "passive"))
    )
    (net (code "88") (name "/MCU_K12") (class "Default")
      (node (ref "Q12") (pin "1") (pinfunction "G_1") (pintype "passive"))
      (node (ref "R12") (pin "2") (pinfunction "2_2") (pintype "passive"))
    )
    (net (code "89") (name "/MCU_K13") (class "Default")
      (node (ref "Q13") (pin "1") (pinfunction "G_1") (pintype "passive"))
      (node (ref "R13") (pin "2") (pinfunction "2_2") (pintype "passive"))
    )
    (net (code "90") (name "/MCU_K14") (class "Default")
      (node (ref "Q14") (pin "1") (pinfunction "G_1") (pintype "passive"))
      (node (ref "R14") (pin "2") (pinfunction "2_2") (pintype "passive"))
    )
    (net (code "91") (name "/MCU_K15") (class "Default")
      (node (ref "Q15") (pin "1") (pinfunction "G_1") (pintype "passive"))
      (node (ref "R15") (pin "2") (pinfunction "2_2") (pintype "passive"))
    )
    (net (code "92") (name "/MCU_K16") (class "Default")
      (node (ref "Q16") (pin "1") (pinfunction "G_1") (pintype "passive"))
      (node (ref "R16") (pin "2") (pinfunction "2_2") (pintype "passive"))
    )
    (net (code "93") (name "/MCU_K17") (class "Default")
      (node (ref "Q17") (pin "1") (pinfunction "G_1") (pintype "passive"))
      (node (ref "R17") (pin "2") (pinfunction "2_2") (pintype "passive"))
    )
    (net (code "94") (name "/MCU_K18") (class "Default")
      (node (ref "Q18") (pin "1") (pinfunction "G_1") (pintype "passive"))
      (node (ref "R18") (pin "2") (pinfunction "2_2") (pintype "passive"))
    )
    (net (code "95") (name "/MCU_K19") (class "Default")
      (node (ref "Q19") (pin "1") (pinfunction "G_1") (pintype "passive"))
      (node (ref "R19") (pin "2") (pinfunction "2_2") (pintype "passive"))
    )
    (net (code "96") (name "/MCU_K20") (class "Default")
      (node (ref "Q20") (pin "1") (pinfunction "G_1") (pintype "passive"))
      (node (ref "R20") (pin "2") (pinfunction "2_2") (pintype "passive"))
    )
    (net (code "97") (name "/MCU_K21") (class "Default")
      (node (ref "Q21") (pin "1") (pinfunction "G_1") (pintype "passive"))
      (node (ref "R21") (pin "2") (pinfunction "2_2") (pintype "passive"))
    )
    (net (code "98") (name "/MCU_K22") (class "Default")
      (node (ref "Q22") (pin "1") (pinfunction "G_1") (pintype "passive"))
      (node (ref "R22") (pin "2") (pinfunction "2_2") (pintype "passive"))
    )
    (net (code "99") (name "/MCU_K23") (class "Default")
      (node (ref "Q23") (pin "1") (pinfunction "G_1") (pintype "passive"))
      (node (ref "R23") (pin "2") (pinfunction "2_2") (pintype "passive"))
    )
    (net (code "100") (name "/MCU_K24") (class "Default")
      (node (ref "Q24") (pin "1") (pinfunction "G_1") (pintype "passive"))
      (node (ref "R24") (pin "2") (pinfunction "2_2") (pintype "passive"))
    )
    (net (code "101") (name "/MCU_MATRIX_EN") (class "Default")
      (node (ref "D32") (pin "4") (pinfunction "EN_4") (pintype "passive"))
      (node (ref "R112") (pin "2") (pinfunction "2_2") (pintype "passive"))
    )
    (net (code "102") (name "GND") (class "Default")
      (node (ref "C2") (pin "1") (pinfunction "1_1") (pintype "passive"))
      (node (ref "C41") (pin "1") (pinfunction "1_1") (pintype "passive"))
      (node (ref "C44") (pin "1") (pinfunction "1_1") (pintype "passive"))
      (node (ref "C45") (pin "1") (pinfunction "1_1") (pintype "passive"))
      (node (ref "D32") (pin "2") (pinfunction "GND_2") (pintype "passive"))
      (node (ref "Q1") (pin "2") (pinfunction "S_2") (pintype "passive"))
      (node (ref "Q10") (pin "2") (pinfunction "S_2") (pintype "passive"))
      (node (ref "Q11") (pin "2") (pinfunction "S_2") (pintype "passive"))
      (node (ref "Q12") (pin "2") (pinfunction "S_2") (pintype "passive"))
      (node (ref "Q13") (pin "2") (pinfunction "S_2") (pintype "passive"))
      (node (ref "Q14") (pin "2") (pinfunction "S_2") (pintype "passive"))
      (node (ref "Q15") (pin "2") (pinfunction "S_2") (pintype "passive"))
      (node (ref "Q16") (pin "2") (pinfunction "S_2") (pintype "passive"))
      (node (ref "Q17") (pin "2") (pinfunction "S_2") (pintype "passive"))
      (node (ref "Q18") (pin "2") (pinfunction "S_2") (pintype "passive"))
      (node (ref "Q19") (pin "2") (pinfunction "S_2") (pintype "passive"))
      (node (ref "Q2") (pin "2") (pinfunction "S_2") (pintype "passive"))
      (node (ref "Q20") (pin "2") (pinfunction "S_2") (pintype "passive"))
      (node (ref "Q21") (pin "2") (pinfunction "S_2") (pintype "passive"))
      (node (ref "Q22") (pin "2") (pinfunction "S_2") (pintype "passive"))
      (node (ref "Q23") (pin "2") (pinfunction "S_2") (pintype "passive"))
      (node (ref "Q24") (pin "2") (pinfunction "S_2") (pintype "passive"))
      (node (ref "Q3") (pin "2") (pinfunction "S_2") (pintype "passive"))
      (node (ref "Q4") (pin "2") (pinfunction "S_2") (pintype "passive"))
      (node (ref "Q5") (pin "2") (pinfunction "S_2") (pintype "passive"))
      (node (ref "Q6") (pin "2") (pinfunction "S_2") (pintype "passive"))
      (node (ref "Q7") (pin "2") (pinfunction "S_2") (pintype "passive"))
      (node (ref "Q8") (pin "2") (pinfunction "S_2") (pintype "passive"))
      (node (ref "Q9") (pin "2") (pinfunction "S_2") (pintype "passive"))
      (node (ref "R1") (pin "1") (pinfunction "1_1") (pintype "passive"))
      (node (ref "R10") (pin "1") (pinfunction "1_1") (pintype "passive"))
      (node (ref "R11") (pin "1") (pinfunction "1_1") (pintype "passive"))
      (node (ref "R111") (pin "1") (pinfunction "1_1") (pintype "passive"))
      (node (ref "R112") (pin "1") (pinfunction "1_1") (pintype "passive"))
      (node (ref "R12") (pin "1") (pinfunction "1_1") (pintype "passive"))
      (node (ref "R13") (pin "1") (pinfunction "1_1") (pintype "passive"))
      (node (ref "R14") (pin "1") (pinfunction "1_1") (pintype "passive"))
      (node (ref "R15") (pin "1") (pinfunction "1_1") (pintype "passive"))
      (node (ref "R16") (pin "1") (pinfunction "1_1") (pintype "passive"))
      (node (ref "R17") (pin "1") (pinfunction "1_1") (pintype "passive"))
      (node (ref "R18") (pin "1") (pinfunction "1_1") (pintype "passive"))
      (node (ref "R19") (pin "1") (pinfunction "1_1") (pintype "passive"))
      (node (ref "R2") (pin "1") (pinfunction "1_1") (pintype "passive"))
      (node (ref "R20") (pin "1") (pinfunction "1_1") (pintype "passive"))
      (node (ref "R21") (pin "1") (pinfunction "1_1") (pintype "passive"))
      (node (ref "R22") (pin "1") (pinfunction "1_1") (pintype "passive"))
      (node (ref "R23") (pin "1") (pinfunction "1_1") (pintype "passive"))
      (node (ref "R24") (pin "1") (pinfunction "1_1") (pintype "passive"))
      (node (ref "R3") (pin "1") (pinfunction "1_1") (pintype "passive"))
      (node (ref "R4") (pin "1") (pinfunction "1_1") (pintype "passive"))
      (node (ref "R5") (pin "1") (pinfunction "1_1") (pintype "passive"))
      (node (ref "R6") (pin "1") (pinfunction "1_1") (pintype "passive"))
      (node (ref "R7") (pin "1") (pinfunction "1_1") (pintype "passive"))
      (node (ref "R8") (pin "1") (pinfunction "1_1") (pintype "passive"))
      (node (ref "R9") (pin "1") (pinfunction "1_1") (pintype "passive"))
    )
    (net (code "103") (name "Net-(D32-FB)") (class "Default")
      (node (ref "C40") (pin "1") (pinfunction "1_1") (pintype "passive"))
      (node (ref "D32") (pin "3") (pinfunction "FB_3") (pintype "passive"))
      (node (ref "R111") (pin "2") (pinfunction "2_2") (pintype "passive"))
      (node (ref "R116") (pin "1") (pinfunction "1_1") (pintype "passive"))
    )
    (net (code "104") (name "Net-(D32-SW)") (class "Default")
      (node (ref "D32") (pin "1") (pinfunction "SW_1") (pintype "passive"))
      (node (ref "D33") (pin "1") (pinfunction "A_1") (pintype "passive"))
      (node (ref "L3") (pin "2") (pinfunction "2_2") (pintype "passive"))
    )
    (net (code "105") (name "Net-(Q25-D)") (class "Default")
      (node (ref "Q25") (pin "3") (pinfunction "D_3") (pintype "passive"))
      (node (ref "R25") (pin "1") (pinfunction "1_1") (pintype "passive"))
    )
    (net (code "106") (name "Net-(Q26-D)") (class "Default")
      (node (ref "Q26") (pin "3") (pinfunction "D_3") (pintype "passive"))
      (node (ref "R26") (pin "1") (pinfunction "1_1") (pintype "passive"))
    )
    (net (code "107") (name "Net-(Q27-D)") (class "Default")
      (node (ref "Q27") (pin "3") (pinfunction "D_3") (pintype "passive"))
      (node (ref "R27") (pin "1") (pinfunction "1_1") (pintype "passive"))
    )
    (net (code "108") (name "Net-(Q28-D)") (class "Default")
      (node (ref "Q28") (pin "3") (pinfunction "D_3") (pintype "passive"))
      (node (ref "R31") (pin "1") (pinfunction "1_1") (pintype "passive"))
    )
    (net (code "109") (name "Net-(Q29-D)") (class "Default")
      (node (ref "Q29") (pin "3") (pinfunction "D_3") (pintype "passive"))
      (node (ref "R32") (pin "1") (pinfunction "1_1") (pintype "passive"))
    )
    (net (code "110") (name "Net-(Q30-D)") (class "Default")
      (node (ref "Q30") (pin "3") (pinfunction "D_3") (pintype "passive"))
      (node (ref "R33") (pin "1") (pinfunction "1_1") (pintype "passive"))
    )
    (net (code "111") (name "Net-(Q31-D)") (class "Default")
      (node (ref "Q31") (pin "3") (pinfunction "D_3") (pintype "passive"))
      (node (ref "R37") (pin "1") (pinfunction "1_1") (pintype "passive"))
    )
    (net (code "112") (name "Net-(Q32-D)") (class "Default")
      (node (ref "Q32") (pin "3") (pinfunction "D_3") (pintype "passive"))
      (node (ref "R38") (pin "1") (pinfunction "1_1") (pintype "passive"))
    )
    (net (code "113") (name "Net-(Q33-D)") (class "Default")
      (node (ref "Q33") (pin "3") (pinfunction "D_3") (pintype "passive"))
      (node (ref "R39") (pin "1") (pinfunction "1_1") (pintype "passive"))
    )
    (net (code "114") (name "Net-(Q34-D)") (class "Default")
      (node (ref "Q34") (pin "3") (pinfunction "D_3") (pintype "passive"))
      (node (ref "R43") (pin "1") (pinfunction "1_1") (pintype "passive"))
    )
    (net (code "115") (name "Net-(Q35-D)") (class "Default")
      (node (ref "Q35") (pin "3") (pinfunction "D_3") (pintype "passive"))
      (node (ref "R44") (pin "1") (pinfunction "1_1") (pintype "passive"))
    )
    (net (code "116") (name "Net-(Q36-D)") (class "Default")
      (node (ref "Q36") (pin "3") (pinfunction "D_3") (pintype "passive"))
      (node (ref "R45") (pin "1") (pinfunction "1_1") (pintype "passive"))
    )
    (net (code "117") (name "Net-(Q37-D)") (class "Default")
      (node (ref "Q37") (pin "3") (pinfunction "D_3") (pintype "passive"))
      (node (ref "R49") (pin "1") (pinfunction "1_1") (pintype "passive"))
    )
    (net (code "118") (name "Net-(Q38-D)") (class "Default")
      (node (ref "Q38") (pin "3") (pinfunction "D_3") (pintype "passive"))
      (node (ref "R50") (pin "1") (pinfunction "1_1") (pintype "passive"))
    )
    (net (code "119") (name "Net-(Q39-D)") (class "Default")
      (node (ref "Q39") (pin "3") (pinfunction "D_3") (pintype "passive"))
      (node (ref "R51") (pin "1") (pinfunction "1_1") (pintype "passive"))
    )
    (net (code "120") (name "Net-(Q40-D)") (class "Default")
      (node (ref "Q40") (pin "3") (pinfunction "D_3") (pintype "passive"))
      (node (ref "R55") (pin "1") (pinfunction "1_1") (pintype "passive"))
    )
    (net (code "121") (name "Net-(Q41-D)") (class "Default")
      (node (ref "Q41") (pin "3") (pinfunction "D_3") (pintype "passive"))
      (node (ref "R56") (pin "1") (pinfunction "1_1") (pintype "passive"))
    )
    (net (code "122") (name "Net-(Q42-D)") (class "Default")
      (node (ref "Q42") (pin "3") (pinfunction "D_3") (pintype "passive"))
      (node (ref "R57") (pin "1") (pinfunction "1_1") (pintype "passive"))
    )
    (net (code "123") (name "Net-(Q43-D)") (class "Default")
      (node (ref "Q43") (pin "3") (pinfunction "D_3") (pintype "passive"))
      (node (ref "R61") (pin "1") (pinfunction "1_1") (pintype "passive"))
    )
    (net (code "124") (name "Net-(Q44-D)") (class "Default")
      (node (ref "Q44") (pin "3") (pinfunction "D_3") (pintype "passive"))
      (node (ref "R62") (pin "1") (pinfunction "1_1") (pintype "passive"))
    )
    (net (code "125") (name "Net-(Q45-D)") (class "Default")
      (node (ref "Q45") (pin "3") (pinfunction "D_3") (pintype "passive"))
      (node (ref "R63") (pin "1") (pinfunction "1_1") (pintype "passive"))
    )
    (net (code "126") (name "Net-(Q46-D)") (class "Default")
      (node (ref "Q46") (pin "3") (pinfunction "D_3") (pintype "passive"))
      (node (ref "R67") (pin "1") (pinfunction "1_1") (pintype "passive"))
    )
    (net (code "127") (name "Net-(Q47-D)") (class "Default")
      (node (ref "Q47") (pin "3") (pinfunction "D_3") (pintype "passive"))
      (node (ref "R68") (pin "1") (pinfunction "1_1") (pintype "passive"))
    )
    (net (code "128") (name "Net-(Q48-D)") (class "Default")
      (node (ref "Q48") (pin "3") (pinfunction "D_3") (pintype "passive"))
      (node (ref "R69") (pin "1") (pinfunction "1_1") (pintype "passive"))
    )
    (net (code "129") (name "Net-(Q49-D)") (class "Default")
      (node (ref "Q49") (pin "3") (pinfunction "D_3") (pintype "passive"))
      (node (ref "R73") (pin "1") (pinfunction "1_1") (pintype "passive"))
    )
    (net (code "130") (name "Net-(Q50-D)") (class "Default")
      (node (ref "Q50") (pin "3") (pinfunction "D_3") (pintype "passive"))
      (node (ref "R74") (pin "1") (pinfunction "1_1") (pintype "passive"))
    )
    (net (code "131") (name "VDD") (class "Default")
      (node (ref "C45") (pin "2") (pinfunction "2_2") (pintype "passive"))
      (node (ref "D32") (pin "5") (pinfunction "Vin_5") (pintype "passive"))
      (node (ref "L3") (pin "1") (pinfunction "1_1") (pintype "passive"))
      (node (ref "R117") (pin "2") (pinfunction "2_2") (pintype "passive"))
    )
    (net (code "132") (name "VDDM") (class "Default")
      (node (ref "C2") (pin "2") (pinfunction "2_2") (pintype "passive"))
      (node (ref "C40") (pin "2") (pinfunction "2_2") (pintype "passive"))
      (node (ref "C41") (pin "2") (pinfunction "2_2") (pintype "passive"))
      (node (ref "C44") (pin "2") (pinfunction "2_2") (pintype "passive"))
      (node (ref "D33") (pin "2") (pinfunction "K_2") (pintype "passive"))
      (node (ref "Q25") (pin "2") (pinfunction "S_2") (pintype "passive"))
      (node (ref "Q26") (pin "2") (pinfunction "S_2") (pintype "passive"))
      (node (ref "Q27") (pin "2") (pinfunction "S_2") (pintype "passive"))
      (node (ref "Q28") (pin "2") (pinfunction "S_2") (pintype "passive"))
      (node (ref "Q29") (pin "2") (pinfunction "S_2") (pintype "passive"))
      (node (ref "Q30") (pin "2") (pinfunction "S_2") (pintype "passive"))
      (node (ref "Q31") (pin "2") (pinfunction "S_2") (pintype "passive"))
      (node (ref "Q32") (pin "2") (pinfunction "S_2") (pintype "passive"))
      (node (ref "Q33") (pin "2") (pinfunction "S_2") (pintype "passive"))
      (node (ref "Q34") (pin "2") (pinfunction "S_2") (pintype "passive"))
      (node (ref "Q35") (pin "2") (pinfunction "S_2") (pintype "passive"))
      (node (ref "Q36") (pin "2") (pinfunction "S_2") (pintype "passive"))
      (node (ref "Q37") (pin "2") (pinfunction "S_2") (pintype "passive"))
      (node (ref "Q38") (pin "2") (pinfunction "S_2") (pintype "passive"))
      (node (ref "Q39") (pin "2") (pinfunction "S_2") (pintype "passive"))
      (node (ref "Q40") (pin "2") (pinfunction "S_2") (pintype "passive"))
      (node (ref "Q41") (pin "2") (pinfunction "S_2") (pintype "passive"))
      (node (ref "Q42") (pin "2") (pinfunction "S_2") (pintype "passive"))
      (node (ref "Q43") (pin "2") (pinfunction "S_2") (pintype "passive"))
      (node (ref "Q44") (pin "2") (pinfunction "S_2") (pintype "passive"))
      (node (ref "Q45") (pin "2") (pinfunction "S_2") (pintype "passive"))
      (node (ref "Q46") (pin "2") (pinfunction "S_2") (pintype "passive"))
      (node (ref "Q47") (pin "2") (pinfunction "S_2") (pintype "passive"))
      (node (ref "Q48") (pin "2") (pinfunction "S_2") (pintype "passive"))
      (node (ref "Q49") (pin "2") (pinfunction "S_2") (pintype "passive"))
      (node (ref "Q50") (pin "2") (pinfunction "S_2") (pintype "passive"))
      (node (ref "R116") (pin "2") (pinfunction "2_2") (pintype "passive"))
      (node (ref "R117") (pin "1") (pinfunction "1_1") (pintype "passive"))
      (node (ref "R28") (pin "1") (pinfunction "1_1") (pintype "passive"))
      (node (ref "R29") (pin "1") (pinfunction "1_1") (pintype "passive"))
      (node (ref "R30") (pin "1") (pinfunction "1_1") (pintype "passive"))
      (node (ref "R34") (pin "1") (pinfunction "1_1") (pintype "passive"))
      (node (ref "R35") (pin "1") (pinfunction "1_1") (pintype "passive"))
      (node (ref "R36") (pin "1") (pinfunction "1_1") (pintype "passive"))
      (node (ref "R40") (pin "1") (pinfunction "1_1") (pintype "passive"))
      (node (ref "R41") (pin "1") (pinfunction "1_1") (pintype "passive"))
      (node (ref "R42") (pin "1") (pinfunction "1_1") (pintype "passive"))
      (node (ref "R46") (pin "1") (pinfunction "1_1") (pintype "passive"))
      (node (ref "R47") (pin "1") (pinfunction "1_1") (pintype "passive"))
      (node (ref "R48") (pin "1") (pinfunction "1_1") (pintype "passive"))
      (node (ref "R52") (pin "1") (pinfunction "1_1") (pintype "passive"))
      (node (ref "R53") (pin "1") (pinfunction "1_1") (pintype "passive"))
      (node (ref "R54") (pin "1") (pinfunction "1_1") (pintype "passive"))
      (node (ref "R58") (pin "1") (pinfunction "1_1") (pintype "passive"))
      (node (ref "R59") (pin "1") (pinfunction "1_1") (pintype "passive"))
      (node (ref "R60") (pin "1") (pinfunction "1_1") (pintype "passive"))
      (node (ref "R64") (pin "1") (pinfunction "1_1") (pintype "passive"))
      (node (ref "R65") (pin "1") (pinfunction "1_1") (pintype "passive"))
      (node (ref "R66") (pin "1") (pinfunction "1_1") (pintype "passive"))
      (node (ref "R70") (pin "1") (pinfunction "1_1") (pintype "passive"))
      (node (ref "R71") (pin "1") (pinfunction "1_1") (pintype "passive"))
      (node (ref "R72") (pin "1") (pinfunction "1_1") (pintype "passive"))
      (node (ref "R75") (pin "1") (pinfunction "1_1") (pintype "passive"))
      (node (ref "R76") (pin "1") (pinfunction "1_1") (pintype "passive"))
    )
  )
)
